# CH32F205RBT6-R1.net
KiCad netlist of a schematic drawn in Altium Designer
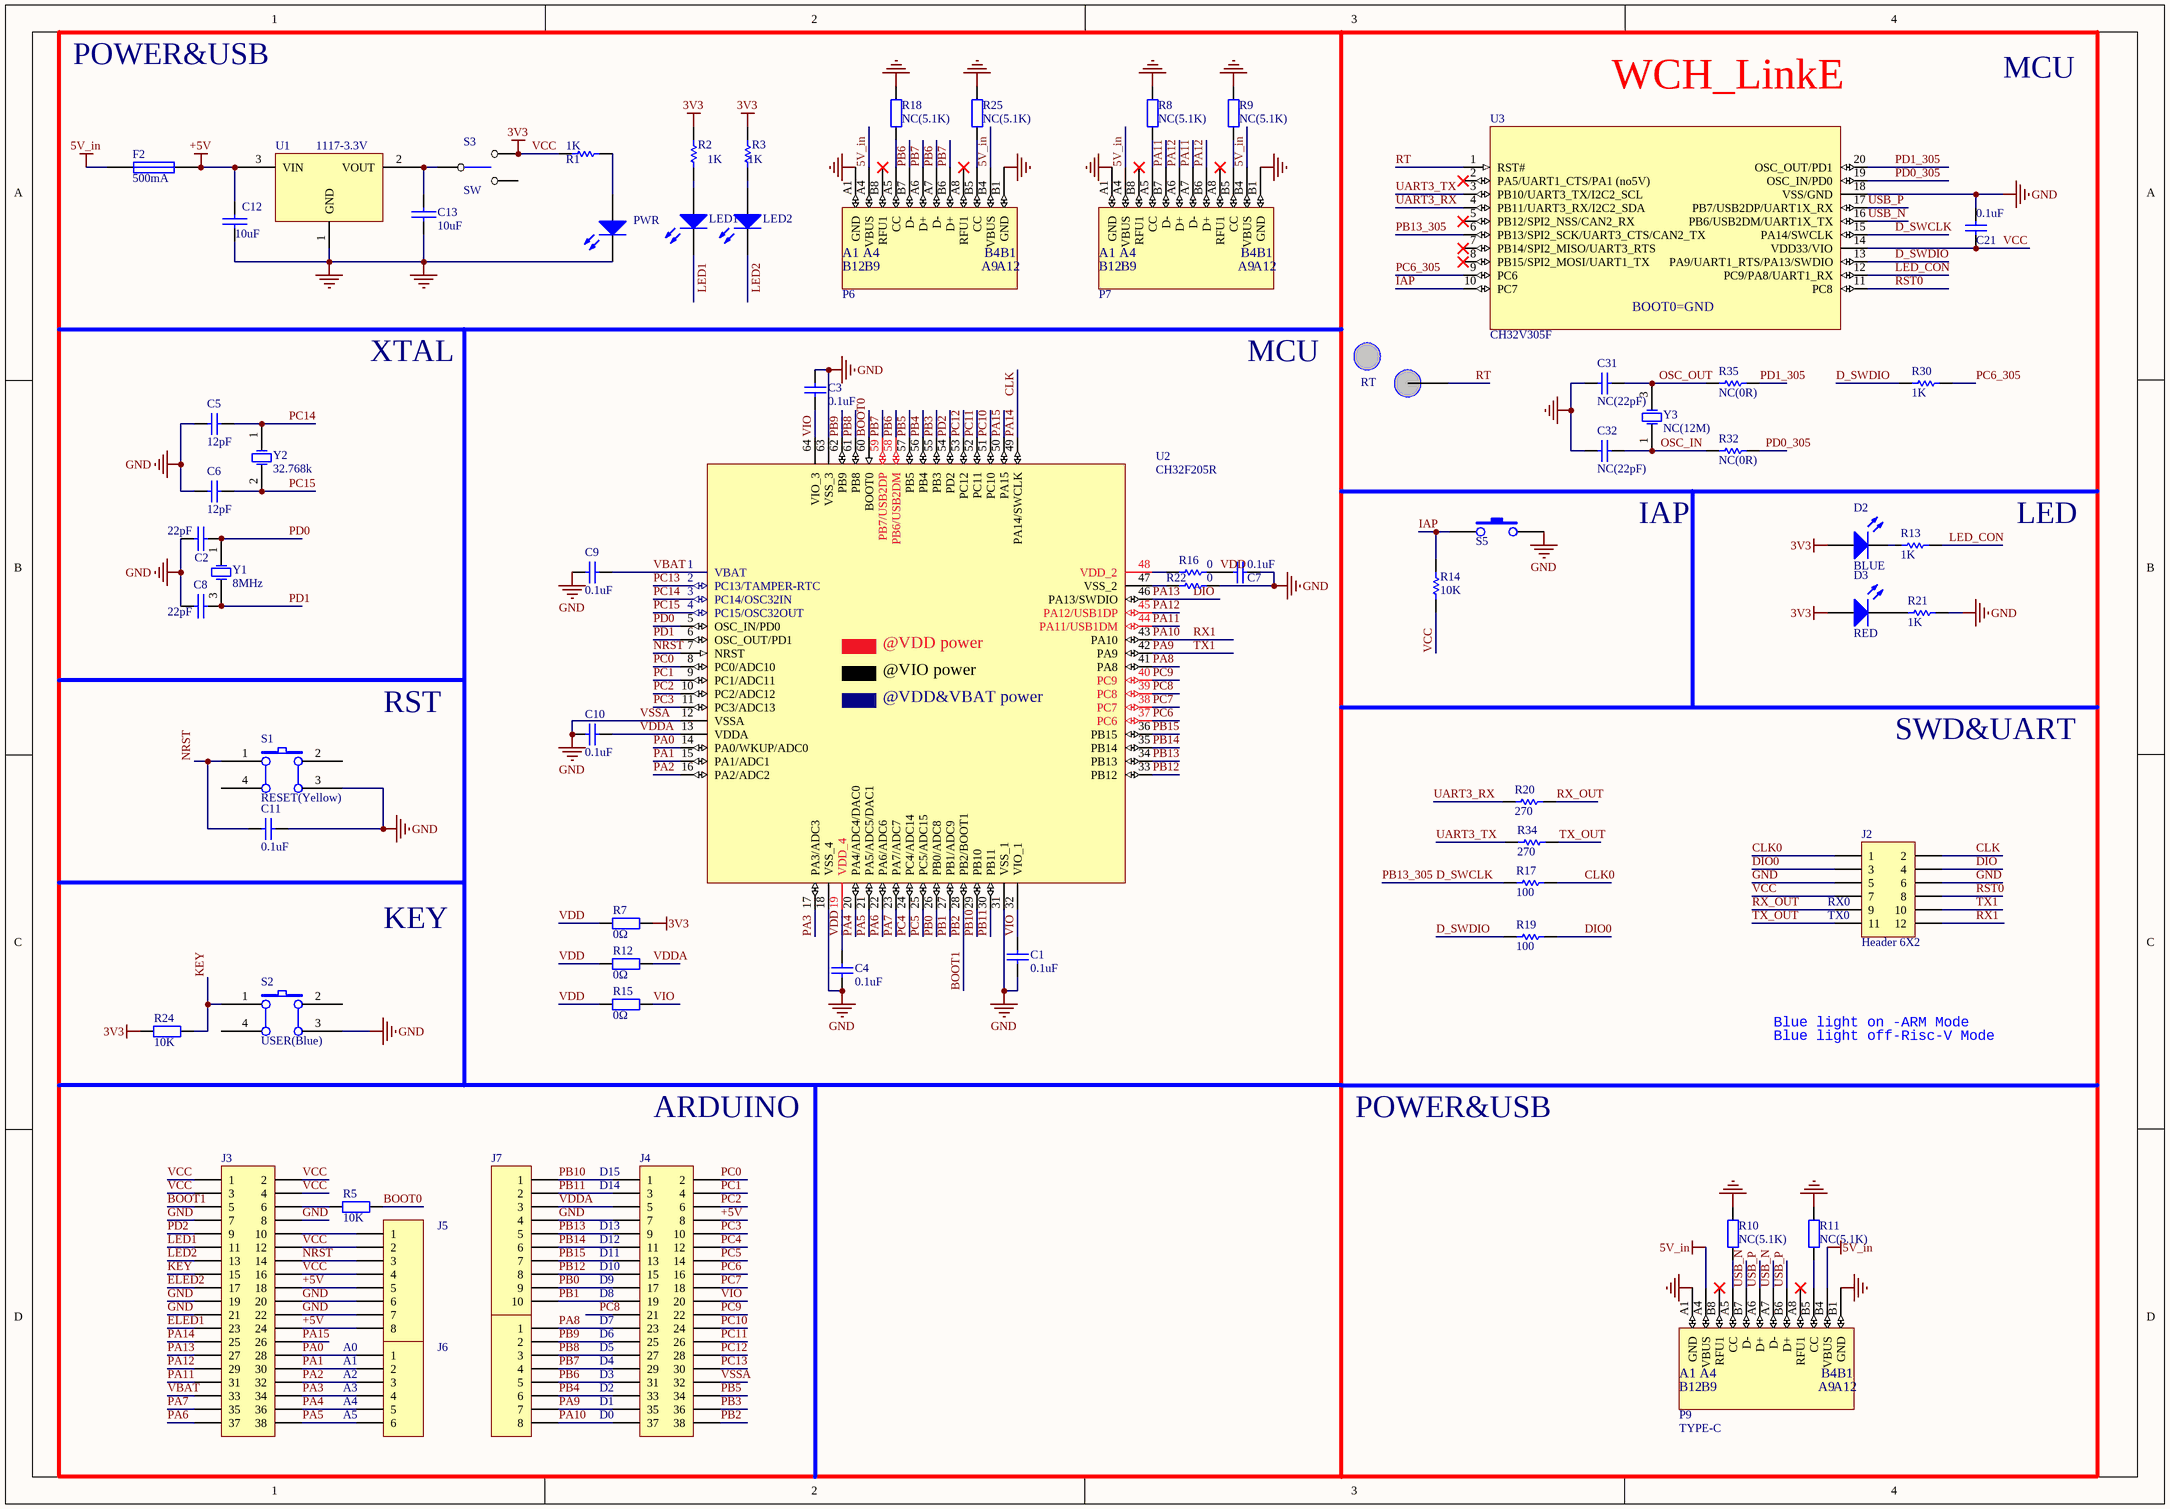
[diagram p0: CH32F205RBT6-R1.SchDoc]

(export (version "E")
  (design (tool "Eeschema 10.0.6"))
  (components
    (comp (ref "C1")
      (value "0.1uF")
      (footprint "0603_C")
      (description "Capacitor")
      (libsource (lib "Miscellaneous Devices") (part "Cap"))
    )
    (comp (ref "C2")
      (value "22pF")
      (footprint "0603_C")
      (description "Capacitor")
      (libsource (lib "*") (part "CAP"))
    )
    (comp (ref "C3")
      (value "0.1uF")
      (footprint "0603_C")
      (description "Capacitor")
      (libsource (lib "Miscellaneous Devices") (part "Cap"))
    )
    (comp (ref "C4")
      (value "0.1uF")
      (footprint "0603_C")
      (description "Capacitor")
      (libsource (lib "Miscellaneous Devices") (part "Cap"))
    )
    (comp (ref "C5")
      (value "12pF")
      (footprint "0603_C")
      (description "Capacitor")
      (libsource (lib "Miscellaneous Devices") (part "Cap"))
    )
    (comp (ref "C6")
      (value "12pF")
      (footprint "0603_C")
      (description "Capacitor")
      (libsource (lib "Miscellaneous Devices") (part "Cap"))
    )
    (comp (ref "C7")
      (value "0.1uF")
      (footprint "0603_C")
      (description "Capacitor")
      (libsource (lib "Miscellaneous Devices") (part "Cap"))
    )
    (comp (ref "C8")
      (value "22pF")
      (footprint "0603_C")
      (description "Capacitor")
      (libsource (lib "*") (part "CAP"))
    )
    (comp (ref "C9")
      (value "0.1uF")
      (footprint "0603_C")
      (description "Capacitor")
      (libsource (lib "Miscellaneous Devices") (part "Cap"))
    )
    (comp (ref "C10")
      (value "0.1uF")
      (footprint "0603_C")
      (description "Capacitor")
      (libsource (lib "Miscellaneous Devices") (part "Cap"))
    )
    (comp (ref "C11")
      (value "0.1uF")
      (footprint "0603_C")
      (description "Capacitor")
      (libsource (lib "Miscellaneous Devices") (part "Cap"))
    )
    (comp (ref "C12")
      (value "10uF")
      (footprint "3216_C")
      (description "Capacitor")
      (libsource (lib "*") (part "CAP"))
    )
    (comp (ref "C13")
      (value "10uF")
      (footprint "3216_C")
      (description "Capacitor")
      (libsource (lib "*") (part "CAP"))
    )
    (comp (ref "C21")
      (value "0.1uF")
      (footprint "0603_C")
      (description "Capacitor")
      (libsource (lib "Miscellaneous Devices") (part "Cap"))
    )
    (comp (ref "C31")
      (value "NC(22pF)")
      (footprint "0603_C")
      (description "Capacitor")
      (fields (field (name "PUBLISHER") "Altium Limited"))
      (libsource (lib "*") (part "Cap"))
    )
    (comp (ref "C32")
      (value "NC(22pF)")
      (footprint "0603_C")
      (description "Capacitor")
      (fields (field (name "PUBLISHER") "Altium Limited"))
      (libsource (lib "*") (part "Cap"))
    )
    (comp (ref "D2")
      (value "BLUE")
      (footprint "0603+")
      (description "Typical RED, GREEN, YELLOW, AMBER GaAs LED")
      (fields (field (name "PUBLISHER") "Altium Limited"))
      (libsource (lib "MYLIB") (part "D0603"))
    )
    (comp (ref "D3")
      (value "RED")
      (footprint "0603+")
      (description "Typical RED, GREEN, YELLOW, AMBER GaAs LED")
      (fields (field (name "PUBLISHER") "Altium Limited"))
      (libsource (lib "MYLIB") (part "D0603"))
    )
    (comp (ref "F2")
      (value "500mA")
      (footprint "0805")
      (description "Fuse")
      (libsource (lib "*") (part "FUSE1"))
    )
    (comp (ref "J2")
      (value "Header 6X2")
      (footprint "IDC12-2.54mm")
      (description "Header, 6-Pin, Dual row")
      (fields (field (name "PUBLISHER") "Altium Limited"))
      (libsource (lib "Miscellaneous Connectors") (part "Header 6X2"))
    )
    (comp (ref "J3")
      (value "Header 19X2")
      (footprint "IDC38-2.54mm")
      (description "Header, 19-Pin, Dual row")
      (fields (field (name "PUBLISHER") "Altium Limited"))
      (libsource (lib "Miscellaneous Connectors") (part "Header 19X2"))
    )
    (comp (ref "J4")
      (value "Header 19X2")
      (footprint "IDC38-2.54mm")
      (description "Header, 19-Pin, Dual row")
      (fields (field (name "PUBLISHER") "Altium Limited"))
      (libsource (lib "Miscellaneous Connectors") (part "Header 19X2"))
    )
    (comp (ref "J5")
      (value "Header 8")
      (footprint "SIP8-2.54mm")
      (description "Header, 8-Pin")
      (fields (field (name "PUBLISHER") "Altium Limited"))
      (libsource (lib "Miscellaneous Connectors") (part "Header 8"))
    )
    (comp (ref "J6")
      (value "Header 6")
      (footprint "SIP6-2.54MM")
      (description "Header, 6-Pin")
      (fields (field (name "PUBLISHER") "Altium Limited"))
      (libsource (lib "Miscellaneous Connectors") (part "Header 6"))
    )
    (comp (ref "J7")
      (value "Header 10")
      (footprint "SIP10-2.54mm")
      (description "Header, 10-Pin")
      (fields (field (name "PUBLISHER") "Altium Limited"))
      (libsource (lib "Miscellaneous Connectors") (part "Header 10"))
    )
    (comp (ref "J8")
      (value "Header 8")
      (footprint "SIP8-2.54mm")
      (description "Header, 8-Pin")
      (fields (field (name "PUBLISHER") "Altium Limited"))
      (libsource (lib "") (part "Header 8_1"))
    )
    (comp (ref "LED1")
      (value "LED1   blue")
      (footprint "0603+")
      (description "Typical INFRARED GaAs LED")
      (fields (field (name "PUBLISHER") "Altium Limited"))
      (libsource (lib "Miscellaneous Devices") (part "LED0"))
    )
    (comp (ref "LED2")
      (value "LED2  blue")
      (footprint "0603+")
      (description "Typical INFRARED GaAs LED")
      (fields (field (name "PUBLISHER") "Altium Limited"))
      (libsource (lib "Miscellaneous Devices") (part "LED0"))
    )
    (comp (ref "P6")
      (value "TYPE-C")
      (footprint "TYPE-C-Receptacle-2.0")
      (libsource (lib "*") (part "TYPE-C1"))
    )
    (comp (ref "P7")
      (value "TYPE-C")
      (footprint "TYPE-C-Receptacle-2.0")
      (libsource (lib "*") (part "TYPE-C1"))
    )
    (comp (ref "P9")
      (value "TYPE-C")
      (footprint "TYPE-C-Receptacle-2.0")
      (libsource (lib "*") (part "TYPE-C1"))
    )
    (comp (ref "PWR")
      (value "POWER  red")
      (footprint "0603+")
      (description "Typical INFRARED GaAs LED")
      (fields (field (name "PUBLISHER") "Altium Limited"))
      (libsource (lib "Miscellaneous Devices") (part "LED0"))
    )
    (comp (ref "R1")
      (value "1K")
      (footprint "0603")
      (description "Semiconductor Resistor")
      (libsource (lib "Miscellaneous Devices") (part "Res Semi"))
    )
    (comp (ref "R2")
      (value "1K")
      (footprint "0603")
      (description "Semiconductor Resistor")
      (libsource (lib "Miscellaneous Devices") (part "Res Semi"))
    )
    (comp (ref "R3")
      (value "1K")
      (footprint "0603")
      (description "Semiconductor Resistor")
      (libsource (lib "Miscellaneous Devices") (part "Res Semi"))
    )
    (comp (ref "R5")
      (value "10K")
      (footprint "0603")
      (description "Resistor")
      (libsource (lib "") (part "Res2_3"))
    )
    (comp (ref "R7")
      (value "0Ω")
      (footprint "0603")
      (description "Resistor")
      (libsource (lib "") (part "Res2_2"))
    )
    (comp (ref "R8")
      (value "NC(5.1K)")
      (footprint "0603")
      (description "Resistor")
      (libsource (lib "Miscellaneous Devices") (part "Res2"))
    )
    (comp (ref "R9")
      (value "NC(5.1K)")
      (footprint "0603")
      (description "Resistor")
      (libsource (lib "Miscellaneous Devices") (part "Res2"))
    )
    (comp (ref "R10")
      (value "NC(5.1K)")
      (footprint "0603")
      (description "Resistor")
      (libsource (lib "") (part "Res2_1"))
    )
    (comp (ref "R11")
      (value "NC(5.1K)")
      (footprint "0603")
      (description "Resistor")
      (libsource (lib "") (part "Res2_1"))
    )
    (comp (ref "R12")
      (value "0Ω")
      (footprint "0603")
      (description "Resistor")
      (libsource (lib "") (part "Res2_2"))
    )
    (comp (ref "R13")
      (value "1K")
      (footprint "0603")
      (description "Resistor")
      (fields (field (name "PUBLISHER") "Altium Limited"))
      (libsource (lib "MYLIB") (part "0603-1"))
    )
    (comp (ref "R14")
      (value "10K")
      (footprint "0603")
      (description "Resistor")
      (fields (field (name "PUBLISHER") "Altium Limited"))
      (libsource (lib "MYLIB") (part "0603-1"))
    )
    (comp (ref "R15")
      (value "0Ω")
      (footprint "0603")
      (description "Resistor")
      (libsource (lib "") (part "Res2_2"))
    )
    (comp (ref "R16")
      (value "0")
      (footprint "0603")
      (description "Resistor")
      (fields (field (name "PUBLISHER") "Altium Limited"))
      (libsource (lib "MYLIB") (part "0603-1"))
    )
    (comp (ref "R17")
      (value "100")
      (footprint "0603")
      (description "Resistor")
      (fields (field (name "PUBLISHER") "Altium Limited"))
      (libsource (lib "MYLIB") (part "0603-1"))
    )
    (comp (ref "R18")
      (value "NC(5.1K)")
      (footprint "0603")
      (description "Resistor")
      (libsource (lib "Miscellaneous Devices") (part "Res2"))
    )
    (comp (ref "R19")
      (value "100")
      (footprint "0603")
      (description "Resistor")
      (fields (field (name "PUBLISHER") "Altium Limited"))
      (libsource (lib "MYLIB") (part "0603-1"))
    )
    (comp (ref "R20")
      (value "270")
      (footprint "0603")
      (description "Resistor")
      (fields (field (name "PUBLISHER") "Altium Limited"))
      (libsource (lib "MYLIB") (part "0603-1"))
    )
    (comp (ref "R21")
      (value "1K")
      (footprint "0603")
      (description "Resistor")
      (fields (field (name "PUBLISHER") "Altium Limited"))
      (libsource (lib "MYLIB") (part "0603-1"))
    )
    (comp (ref "R22")
      (value "0")
      (footprint "0603")
      (description "Resistor")
      (fields (field (name "PUBLISHER") "Altium Limited"))
      (libsource (lib "MYLIB") (part "0603-1"))
    )
    (comp (ref "R24")
      (value "10K")
      (footprint "0603")
      (description "Resistor")
      (libsource (lib "") (part "Res2_2"))
    )
    (comp (ref "R25")
      (value "NC(5.1K)")
      (footprint "0603")
      (description "Resistor")
      (libsource (lib "Miscellaneous Devices") (part "Res2"))
    )
    (comp (ref "R30")
      (value "1K")
      (footprint "0603")
      (description "Resistor")
      (fields (field (name "PUBLISHER") "Altium Limited"))
      (libsource (lib "MYLIB") (part "0603-1"))
    )
    (comp (ref "R32")
      (value "NC(0R)")
      (footprint "0603")
      (description "Resistor")
      (fields (field (name "PUBLISHER") "Altium Limited"))
      (libsource (lib "MYLIB") (part "0603-1"))
    )
    (comp (ref "R34")
      (value "270")
      (footprint "0603")
      (description "Resistor")
      (fields (field (name "PUBLISHER") "Altium Limited"))
      (libsource (lib "MYLIB") (part "0603-1"))
    )
    (comp (ref "R35")
      (value "NC(0R)")
      (footprint "0603")
      (description "Resistor")
      (fields (field (name "PUBLISHER") "Altium Limited"))
      (libsource (lib "MYLIB") (part "0603-1"))
    )
    (comp (ref "RT")
      (value "Testpoint")
      (footprint "TESTPOINT1")
      (description "测试点")
      (libsource (lib "wch_sch_others") (part "Testpoint"))
    )
    (comp (ref "S1")
      (value "RESET(Yellow)")
      (footprint "KEYX")
      (description "SE PUSHBUTTON")
      (libsource (lib "Documents") (part "SW PUSHBUTTON"))
    )
    (comp (ref "S2")
      (value "USER(Blue)")
      (footprint "KEYX")
      (description "SE PUSHBUTTON")
      (libsource (lib "Documents") (part "SW PUSHBUTTON"))
    )
    (comp (ref "S3") (value "SW") (footprint "SW1") (libsource (lib "MYSCH") (part "SW")))
    (comp (ref "S5") (value "KEY") (footprint "贴片按键") (libsource (lib "*") (part "KEY")))
    (comp (ref "U1")
      (value "1117-3.3V")
      (footprint "SOT-223")
      (libsource (lib "wch_sch_others") (part "1117-3.3V"))
    )
    (comp (ref "U2")
      (value "CH32F205R")
      (footprint "LQFP64M_10x10")
      (description "ARM M3 HD-MCU, 144MHz, USB_480M, USB OTG, 2*CAN, 4*OPA")
      (libsource (lib "CHXXX") (part "CH32F205R"))
    )
    (comp (ref "U3")
      (value "CH32V305F")
      (footprint "TSSOP20")
      (description "RISC-V FPU HD-MCU, 144MHz, USB_480M, CAN, UART*2, SPI")
      (libsource (lib "CHXXX") (part "CH32V305F"))
    )
    (comp (ref "Y1")
      (value "8MHz")
      (footprint "XT3225")
      (description "Crystal Oscillator")
      (fields (field (name "PUBLISHER") "Altium Limited"))
      (libsource (lib "*") (part "XTAL"))
    )
    (comp (ref "Y2")
      (value "32.768k")
      (footprint "FC-135")
      (description "Crystal Oscillator")
      (fields (field (name "PUBLISHER") "Altium Limited"))
      (libsource (lib "Miscellaneous Devices") (part "XTAL"))
    )
    (comp (ref "Y3")
      (value "NC(12M)")
      (footprint "XT3225")
      (description "Crystal Oscillator")
      (libsource (lib "*") (part "XTAL"))
    )
  )
  (nets
    (net (code "1") (name "+5V") (class "Default")
      (node (ref "C12") (pin "1") (pinfunction "1_1") (pintype "passive"))
      (node (ref "F2") (pin "2") (pinfunction "2_2") (pintype "passive"))
      (node (ref "J3") (pin "18") (pinfunction "18_18") (pintype "passive"))
      (node (ref "J3") (pin "24") (pinfunction "24_24") (pintype "passive"))
      (node (ref "J4") (pin "8") (pinfunction "8_8") (pintype "passive"))
      (node (ref "J5") (pin "5") (pinfunction "5_5") (pintype "passive"))
      (node (ref "J5") (pin "8") (pinfunction "8_8") (pintype "passive"))
      (node (ref "U1") (pin "3") (pinfunction "VIN_3") (pintype "passive"))
    )
    (net (code "2") (name "/BOOT0") (class "Default")
      (node (ref "R5") (pin "2") (pinfunction "2_2") (pintype "passive"))
      (node (ref "U2") (pin "60") (pinfunction "BOOT0_60") (pintype "input"))
    )
    (net (code "3") (name "/BOOT1") (class "Default")
      (node (ref "J3") (pin "5") (pinfunction "5_5") (pintype "passive"))
      (node (ref "J4") (pin "38") (pinfunction "38_38") (pintype "passive"))
      (node (ref "U2") (pin "28") (pinfunction "PB2/BOOT1_28") (pintype "bidirectional"))
    )
    (net (code "4") (name "/CLK") (class "Default")
      (node (ref "J2") (pin "2") (pinfunction "2_2") (pintype "passive"))
      (node (ref "J3") (pin "25") (pinfunction "25_25") (pintype "passive"))
      (node (ref "U2") (pin "49") (pinfunction "PA14/SWCLK_49") (pintype "bidirectional"))
    )
    (net (code "5") (name "/CLK0") (class "Default")
      (node (ref "J2") (pin "1") (pinfunction "1_1") (pintype "passive"))
      (node (ref "R17") (pin "1") (pinfunction "1_1") (pintype "passive"))
    )
    (net (code "6") (name "/DIO") (class "Default")
      (node (ref "J2") (pin "4") (pinfunction "4_4") (pintype "passive"))
      (node (ref "J3") (pin "27") (pinfunction "27_27") (pintype "passive"))
      (node (ref "U2") (pin "46") (pinfunction "PA13/SWDIO_46") (pintype "bidirectional"))
    )
    (net (code "7") (name "/DIO0") (class "Default")
      (node (ref "J2") (pin "3") (pinfunction "3_3") (pintype "passive"))
      (node (ref "R19") (pin "1") (pinfunction "1_1") (pintype "passive"))
    )
    (net (code "8") (name "/D_SWCLK") (class "Default")
      (node (ref "R17") (pin "2") (pinfunction "2_2") (pintype "passive"))
      (node (ref "U3") (pin "15") (pinfunction "PA14/SWCLK_15") (pintype "bidirectional"))
      (node (ref "U3") (pin "6") (pinfunction "PB13/SPI2_SCK/UART3_CTS/CAN2_TX_6") (pintype "bidirectional"))
    )
    (net (code "9") (name "/D_SWDIO") (class "Default")
      (node (ref "R19") (pin "2") (pinfunction "2_2") (pintype "passive"))
      (node (ref "R30") (pin "1") (pinfunction "1_1") (pintype "passive"))
      (node (ref "U3") (pin "13") (pinfunction "PA9/UART1_RTS/PA13/SWDIO_13") (pintype "bidirectional"))
    )
    (net (code "10") (name "/ELED1") (class "Default")
      (node (ref "J3") (pin "23") (pinfunction "23_23") (pintype "passive"))
    )
    (net (code "11") (name "/ELED2") (class "Default")
      (node (ref "J3") (pin "17") (pinfunction "17_17") (pintype "passive"))
    )
    (net (code "12") (name "/IAP") (class "Default")
      (node (ref "R14") (pin "1") (pinfunction "1_1") (pintype "passive"))
      (node (ref "S5") (pin "1") (pinfunction "1_1") (pintype "passive"))
      (node (ref "U3") (pin "10") (pinfunction "PC7_10") (pintype "bidirectional"))
    )
    (net (code "13") (name "/KEY") (class "Default")
      (node (ref "J3") (pin "15") (pinfunction "15_15") (pintype "passive"))
      (node (ref "R24") (pin "1") (pinfunction "1_1") (pintype "passive"))
      (node (ref "S2") (pin "1") (pinfunction "A0_1") (pintype "passive"))
    )
    (net (code "14") (name "/LED1") (class "Default")
      (node (ref "J3") (pin "11") (pinfunction "11_11") (pintype "passive"))
      (node (ref "LED1") (pin "2") (pinfunction "K_2") (pintype "passive"))
    )
    (net (code "15") (name "/LED2") (class "Default")
      (node (ref "J3") (pin "13") (pinfunction "13_13") (pintype "passive"))
      (node (ref "LED2") (pin "2") (pinfunction "K_2") (pintype "passive"))
    )
    (net (code "16") (name "/LED_CON") (class "Default")
      (node (ref "R13") (pin "1") (pinfunction "1_1") (pintype "passive"))
      (node (ref "U3") (pin "12") (pinfunction "PC9/PA8/UART1_RX_12") (pintype "bidirectional"))
    )
    (net (code "17") (name "/NRST") (class "Default")
      (node (ref "C11") (pin "2") (pinfunction "2_2") (pintype "passive"))
      (node (ref "J3") (pin "14") (pinfunction "14_14") (pintype "passive"))
      (node (ref "J5") (pin "3") (pinfunction "3_3") (pintype "passive"))
      (node (ref "S1") (pin "1") (pinfunction "A0_1") (pintype "passive"))
      (node (ref "U2") (pin "7") (pinfunction "NRST_7") (pintype "input"))
    )
    (net (code "18") (name "/OSC_IN") (class "Default")
      (node (ref "C32") (pin "2") (pinfunction "2_2") (pintype "passive"))
      (node (ref "R32") (pin "2") (pinfunction "2_2") (pintype "passive"))
      (node (ref "Y3") (pin "1") (pinfunction "OSC1_1") (pintype "passive"))
    )
    (net (code "19") (name "/OSC_OUT") (class "Default")
      (node (ref "C31") (pin "2") (pinfunction "2_2") (pintype "passive"))
      (node (ref "R35") (pin "2") (pinfunction "2_2") (pintype "passive"))
      (node (ref "Y3") (pin "3") (pinfunction "OSC2_3") (pintype "passive"))
    )
    (net (code "20") (name "/PA0") (class "Default")
      (node (ref "J3") (pin "28") (pinfunction "28_28") (pintype "passive"))
      (node (ref "J6") (pin "1") (pinfunction "1_1") (pintype "passive"))
      (node (ref "U2") (pin "14") (pinfunction "PA0/WKUP/ADC0_14") (pintype "bidirectional"))
    )
    (net (code "21") (name "/PA1") (class "Default")
      (node (ref "J3") (pin "30") (pinfunction "30_30") (pintype "passive"))
      (node (ref "J6") (pin "2") (pinfunction "2_2") (pintype "passive"))
      (node (ref "U2") (pin "15") (pinfunction "PA1/ADC1_15") (pintype "bidirectional"))
    )
    (net (code "22") (name "/PA2") (class "Default")
      (node (ref "J3") (pin "32") (pinfunction "32_32") (pintype "passive"))
      (node (ref "J6") (pin "3") (pinfunction "3_3") (pintype "passive"))
      (node (ref "U2") (pin "16") (pinfunction "PA2/ADC2_16") (pintype "bidirectional"))
    )
    (net (code "23") (name "/PA3") (class "Default")
      (node (ref "J3") (pin "34") (pinfunction "34_34") (pintype "passive"))
      (node (ref "J6") (pin "4") (pinfunction "4_4") (pintype "passive"))
      (node (ref "U2") (pin "17") (pinfunction "PA3/ADC3_17") (pintype "bidirectional"))
    )
    (net (code "24") (name "/PA4") (class "Default")
      (node (ref "J3") (pin "36") (pinfunction "36_36") (pintype "passive"))
      (node (ref "J6") (pin "5") (pinfunction "5_5") (pintype "passive"))
      (node (ref "U2") (pin "20") (pinfunction "PA4/ADC4/DAC0_20") (pintype "bidirectional"))
    )
    (net (code "25") (name "/PA5") (class "Default")
      (node (ref "J3") (pin "38") (pinfunction "38_38") (pintype "passive"))
      (node (ref "J6") (pin "6") (pinfunction "6_6") (pintype "passive"))
      (node (ref "U2") (pin "21") (pinfunction "PA5/ADC5/DAC1_21") (pintype "bidirectional"))
    )
    (net (code "26") (name "/PA6") (class "Default")
      (node (ref "J3") (pin "37") (pinfunction "37_37") (pintype "passive"))
      (node (ref "U2") (pin "22") (pinfunction "PA6/ADC6_22") (pintype "bidirectional"))
    )
    (net (code "27") (name "/PA7") (class "Default")
      (node (ref "J3") (pin "35") (pinfunction "35_35") (pintype "passive"))
      (node (ref "U2") (pin "23") (pinfunction "PA7/ADC7_23") (pintype "bidirectional"))
    )
    (net (code "28") (name "/PA8") (class "Default")
      (node (ref "J4") (pin "23") (pinfunction "23_23") (pintype "passive"))
      (node (ref "J8") (pin "1") (pinfunction "1_1") (pintype "passive"))
      (node (ref "U2") (pin "41") (pinfunction "PA8_41") (pintype "bidirectional"))
    )
    (net (code "29") (name "/PA9") (class "Default")
      (node (ref "J2") (pin "10") (pinfunction "10_10") (pintype "passive"))
      (node (ref "J4") (pin "35") (pinfunction "35_35") (pintype "passive"))
      (node (ref "J8") (pin "7") (pinfunction "7_7") (pintype "passive"))
      (node (ref "U2") (pin "42") (pinfunction "PA9_42") (pintype "bidirectional"))
    )
    (net (code "30") (name "/PA10") (class "Default")
      (node (ref "J2") (pin "12") (pinfunction "12_12") (pintype "passive"))
      (node (ref "J4") (pin "37") (pinfunction "37_37") (pintype "passive"))
      (node (ref "J8") (pin "8") (pinfunction "8_8") (pintype "passive"))
      (node (ref "U2") (pin "43") (pinfunction "PA10_43") (pintype "bidirectional"))
    )
    (net (code "31") (name "/PA11") (class "Default")
      (node (ref "J3") (pin "31") (pinfunction "31_31") (pintype "passive"))
      (node (ref "P7") (pin "A7") (pinfunction "D-_A7") (pintype "bidirectional"))
      (node (ref "P7") (pin "B7") (pinfunction "D-_B7") (pintype "bidirectional"))
      (node (ref "U2") (pin "44") (pinfunction "PA11/USB1DM_44") (pintype "bidirectional"))
    )
    (net (code "32") (name "/PA12") (class "Default")
      (node (ref "J3") (pin "29") (pinfunction "29_29") (pintype "passive"))
      (node (ref "P7") (pin "A6") (pinfunction "D+_A6") (pintype "bidirectional"))
      (node (ref "P7") (pin "B6") (pinfunction "D+_B6") (pintype "bidirectional"))
      (node (ref "U2") (pin "45") (pinfunction "PA12/USB1DP_45") (pintype "bidirectional"))
    )
    (net (code "33") (name "/PA15") (class "Default")
      (node (ref "J3") (pin "26") (pinfunction "26_26") (pintype "passive"))
      (node (ref "U2") (pin "50") (pinfunction "PA15_50") (pintype "bidirectional"))
    )
    (net (code "34") (name "/PB0") (class "Default")
      (node (ref "J4") (pin "17") (pinfunction "17_17") (pintype "passive"))
      (node (ref "J7") (pin "9") (pinfunction "9_9") (pintype "passive"))
      (node (ref "U2") (pin "26") (pinfunction "PB0/ADC8_26") (pintype "bidirectional"))
    )
    (net (code "35") (name "/PB1") (class "Default")
      (node (ref "J4") (pin "19") (pinfunction "19_19") (pintype "passive"))
      (node (ref "J7") (pin "10") (pinfunction "10_10") (pintype "passive"))
      (node (ref "U2") (pin "27") (pinfunction "PB1/ADC9_27") (pintype "bidirectional"))
    )
    (net (code "36") (name "/PB3") (class "Default")
      (node (ref "J4") (pin "36") (pinfunction "36_36") (pintype "passive"))
      (node (ref "U2") (pin "55") (pinfunction "PB3_55") (pintype "bidirectional"))
    )
    (net (code "37") (name "/PB4") (class "Default")
      (node (ref "J4") (pin "33") (pinfunction "33_33") (pintype "passive"))
      (node (ref "J8") (pin "6") (pinfunction "6_6") (pintype "passive"))
      (node (ref "U2") (pin "56") (pinfunction "PB4_56") (pintype "bidirectional"))
    )
    (net (code "38") (name "/PB5") (class "Default")
      (node (ref "J4") (pin "34") (pinfunction "34_34") (pintype "passive"))
      (node (ref "U2") (pin "57") (pinfunction "PB5_57") (pintype "bidirectional"))
    )
    (net (code "39") (name "/PB6") (class "Default")
      (node (ref "J4") (pin "31") (pinfunction "31_31") (pintype "passive"))
      (node (ref "J8") (pin "5") (pinfunction "5_5") (pintype "passive"))
      (node (ref "P6") (pin "A7") (pinfunction "D-_A7") (pintype "bidirectional"))
      (node (ref "P6") (pin "B7") (pinfunction "D-_B7") (pintype "bidirectional"))
      (node (ref "U2") (pin "58") (pinfunction "PB6/USB2DM_58") (pintype "bidirectional"))
    )
    (net (code "40") (name "/PB7") (class "Default")
      (node (ref "J4") (pin "29") (pinfunction "29_29") (pintype "passive"))
      (node (ref "J8") (pin "4") (pinfunction "4_4") (pintype "passive"))
      (node (ref "P6") (pin "A6") (pinfunction "D+_A6") (pintype "bidirectional"))
      (node (ref "P6") (pin "B6") (pinfunction "D+_B6") (pintype "bidirectional"))
      (node (ref "U2") (pin "59") (pinfunction "PB7/USB2DP_59") (pintype "bidirectional"))
    )
    (net (code "41") (name "/PB8") (class "Default")
      (node (ref "J4") (pin "27") (pinfunction "27_27") (pintype "passive"))
      (node (ref "J8") (pin "3") (pinfunction "3_3") (pintype "passive"))
      (node (ref "U2") (pin "61") (pinfunction "PB8_61") (pintype "bidirectional"))
    )
    (net (code "42") (name "/PB9") (class "Default")
      (node (ref "J4") (pin "25") (pinfunction "25_25") (pintype "passive"))
      (node (ref "J8") (pin "2") (pinfunction "2_2") (pintype "passive"))
      (node (ref "U2") (pin "62") (pinfunction "PB9_62") (pintype "bidirectional"))
    )
    (net (code "43") (name "/PB10") (class "Default")
      (node (ref "J4") (pin "1") (pinfunction "1_1") (pintype "passive"))
      (node (ref "J7") (pin "1") (pinfunction "1_1") (pintype "passive"))
      (node (ref "U2") (pin "29") (pinfunction "PB10_29") (pintype "bidirectional"))
    )
    (net (code "44") (name "/PB11") (class "Default")
      (node (ref "J4") (pin "3") (pinfunction "3_3") (pintype "passive"))
      (node (ref "J7") (pin "2") (pinfunction "2_2") (pintype "passive"))
      (node (ref "U2") (pin "30") (pinfunction "PB11_30") (pintype "bidirectional"))
    )
    (net (code "45") (name "/PB12") (class "Default")
      (node (ref "J4") (pin "15") (pinfunction "15_15") (pintype "passive"))
      (node (ref "J7") (pin "8") (pinfunction "8_8") (pintype "passive"))
      (node (ref "U2") (pin "33") (pinfunction "PB12_33") (pintype "bidirectional"))
    )
    (net (code "46") (name "/PB13") (class "Default")
      (node (ref "J4") (pin "9") (pinfunction "9_9") (pintype "passive"))
      (node (ref "J7") (pin "5") (pinfunction "5_5") (pintype "passive"))
      (node (ref "U2") (pin "34") (pinfunction "PB13_34") (pintype "bidirectional"))
    )
    (net (code "47") (name "/PB14") (class "Default")
      (node (ref "J4") (pin "11") (pinfunction "11_11") (pintype "passive"))
      (node (ref "J7") (pin "6") (pinfunction "6_6") (pintype "passive"))
      (node (ref "U2") (pin "35") (pinfunction "PB14_35") (pintype "bidirectional"))
    )
    (net (code "48") (name "/PB15") (class "Default")
      (node (ref "J4") (pin "13") (pinfunction "13_13") (pintype "passive"))
      (node (ref "J7") (pin "7") (pinfunction "7_7") (pintype "passive"))
      (node (ref "U2") (pin "36") (pinfunction "PB15_36") (pintype "bidirectional"))
    )
    (net (code "49") (name "/PC0") (class "Default")
      (node (ref "J4") (pin "2") (pinfunction "2_2") (pintype "passive"))
      (node (ref "U2") (pin "8") (pinfunction "PC0/ADC10_8") (pintype "bidirectional"))
    )
    (net (code "50") (name "/PC1") (class "Default")
      (node (ref "J4") (pin "4") (pinfunction "4_4") (pintype "passive"))
      (node (ref "U2") (pin "9") (pinfunction "PC1/ADC11_9") (pintype "bidirectional"))
    )
    (net (code "51") (name "/PC2") (class "Default")
      (node (ref "J4") (pin "6") (pinfunction "6_6") (pintype "passive"))
      (node (ref "U2") (pin "10") (pinfunction "PC2/ADC12_10") (pintype "bidirectional"))
    )
    (net (code "52") (name "/PC3") (class "Default")
      (node (ref "J4") (pin "10") (pinfunction "10_10") (pintype "passive"))
      (node (ref "U2") (pin "11") (pinfunction "PC3/ADC13_11") (pintype "bidirectional"))
    )
    (net (code "53") (name "/PC4") (class "Default")
      (node (ref "J4") (pin "12") (pinfunction "12_12") (pintype "passive"))
      (node (ref "U2") (pin "24") (pinfunction "PC4/ADC14_24") (pintype "bidirectional"))
    )
    (net (code "54") (name "/PC5") (class "Default")
      (node (ref "J4") (pin "14") (pinfunction "14_14") (pintype "passive"))
      (node (ref "U2") (pin "25") (pinfunction "PC5/ADC15_25") (pintype "bidirectional"))
    )
    (net (code "55") (name "/PC6") (class "Default")
      (node (ref "J4") (pin "16") (pinfunction "16_16") (pintype "passive"))
      (node (ref "U2") (pin "37") (pinfunction "PC6_37") (pintype "bidirectional"))
    )
    (net (code "56") (name "/PC6_305") (class "Default")
      (node (ref "R30") (pin "2") (pinfunction "2_2") (pintype "passive"))
      (node (ref "U3") (pin "9") (pinfunction "PC6_9") (pintype "bidirectional"))
    )
    (net (code "57") (name "/PC7") (class "Default")
      (node (ref "J4") (pin "18") (pinfunction "18_18") (pintype "passive"))
      (node (ref "U2") (pin "38") (pinfunction "PC7_38") (pintype "bidirectional"))
    )
    (net (code "58") (name "/PC8") (class "Default")
      (node (ref "J4") (pin "21") (pinfunction "21_21") (pintype "passive"))
      (node (ref "U2") (pin "39") (pinfunction "PC8_39") (pintype "bidirectional"))
    )
    (net (code "59") (name "/PC9") (class "Default")
      (node (ref "J4") (pin "22") (pinfunction "22_22") (pintype "passive"))
      (node (ref "U2") (pin "40") (pinfunction "PC9_40") (pintype "bidirectional"))
    )
    (net (code "60") (name "/PC10") (class "Default")
      (node (ref "J4") (pin "24") (pinfunction "24_24") (pintype "passive"))
      (node (ref "U2") (pin "51") (pinfunction "PC10_51") (pintype "bidirectional"))
    )
    (net (code "61") (name "/PC11") (class "Default")
      (node (ref "J4") (pin "26") (pinfunction "26_26") (pintype "passive"))
      (node (ref "U2") (pin "52") (pinfunction "PC11_52") (pintype "bidirectional"))
    )
    (net (code "62") (name "/PC12") (class "Default")
      (node (ref "J4") (pin "28") (pinfunction "28_28") (pintype "passive"))
      (node (ref "U2") (pin "53") (pinfunction "PC12_53") (pintype "bidirectional"))
    )
    (net (code "63") (name "/PC13") (class "Default")
      (node (ref "J4") (pin "30") (pinfunction "30_30") (pintype "passive"))
      (node (ref "U2") (pin "2") (pinfunction "PC13/TAMPER-RTC_2") (pintype "bidirectional"))
    )
    (net (code "64") (name "/PC14") (class "Default")
      (node (ref "C5") (pin "1") (pinfunction "1_1") (pintype "passive"))
      (node (ref "U2") (pin "3") (pinfunction "PC14/OSC32IN_3") (pintype "bidirectional"))
      (node (ref "Y2") (pin "1") (pinfunction "OSC1_1") (pintype "passive"))
    )
    (net (code "65") (name "/PC15") (class "Default")
      (node (ref "C6") (pin "1") (pinfunction "1_1") (pintype "passive"))
      (node (ref "U2") (pin "4") (pinfunction "PC15/OSC32OUT_4") (pintype "bidirectional"))
      (node (ref "Y2") (pin "2") (pinfunction "OSC2_2") (pintype "passive"))
    )
    (net (code "66") (name "/PD0") (class "Default")
      (node (ref "C2") (pin "2") (pinfunction "2_2") (pintype "passive"))
      (node (ref "U2") (pin "5") (pinfunction "OSC_IN/PD0_5") (pintype "bidirectional"))
      (node (ref "Y1") (pin "1") (pinfunction "OSC1_1") (pintype "passive"))
    )
    (net (code "67") (name "/PD0_305") (class "Default")
      (node (ref "R32") (pin "1") (pinfunction "1_1") (pintype "passive"))
      (node (ref "U3") (pin "19") (pinfunction "OSC_IN/PD0_19") (pintype "bidirectional"))
    )
    (net (code "68") (name "/PD1") (class "Default")
      (node (ref "C8") (pin "2") (pinfunction "2_2") (pintype "passive"))
      (node (ref "U2") (pin "6") (pinfunction "OSC_OUT/PD1_6") (pintype "bidirectional"))
      (node (ref "Y1") (pin "3") (pinfunction "OSC2_3") (pintype "passive"))
    )
    (net (code "69") (name "/PD1_305") (class "Default")
      (node (ref "R35") (pin "1") (pinfunction "1_1") (pintype "passive"))
      (node (ref "U3") (pin "20") (pinfunction "OSC_OUT/PD1_20") (pintype "bidirectional"))
    )
    (net (code "70") (name "/PD2") (class "Default")
      (node (ref "J3") (pin "9") (pinfunction "9_9") (pintype "passive"))
      (node (ref "U2") (pin "54") (pinfunction "PD2_54") (pintype "bidirectional"))
    )
    (net (code "71") (name "/RST0") (class "Default")
      (node (ref "J2") (pin "8") (pinfunction "8_8") (pintype "passive"))
      (node (ref "U3") (pin "11") (pinfunction "PC8_11") (pintype "bidirectional"))
    )
    (net (code "72") (name "/RT") (class "Default")
      (node (ref "RT") (pin "1") (pinfunction "point_1") (pintype "passive"))
      (node (ref "U3") (pin "1") (pinfunction "RST#_1") (pintype "input"))
    )
    (net (code "73") (name "/RX_OUT") (class "Default")
      (node (ref "J2") (pin "9") (pinfunction "9_9") (pintype "passive"))
      (node (ref "R20") (pin "1") (pinfunction "1_1") (pintype "passive"))
    )
    (net (code "74") (name "/TX_OUT") (class "Default")
      (node (ref "J2") (pin "11") (pinfunction "11_11") (pintype "passive"))
      (node (ref "R34") (pin "1") (pinfunction "1_1") (pintype "passive"))
    )
    (net (code "75") (name "/UART3_RX") (class "Default")
      (node (ref "R20") (pin "2") (pinfunction "2_2") (pintype "passive"))
      (node (ref "U3") (pin "4") (pinfunction "PB11/UART3_RX/I2C2_SDA_4") (pintype "bidirectional"))
    )
    (net (code "76") (name "/UART3_TX") (class "Default")
      (node (ref "R34") (pin "2") (pinfunction "2_2") (pintype "passive"))
      (node (ref "U3") (pin "3") (pinfunction "PB10/UART3_TX/I2C2_SCL_3") (pintype "bidirectional"))
    )
    (net (code "77") (name "/USB_N") (class "Default")
      (node (ref "P9") (pin "A7") (pinfunction "D-_A7") (pintype "bidirectional"))
      (node (ref "P9") (pin "B7") (pinfunction "D-_B7") (pintype "bidirectional"))
      (node (ref "U3") (pin "16") (pinfunction "PB6/USB2DM/UART1X_TX_16") (pintype "bidirectional"))
    )
    (net (code "78") (name "/USB_P") (class "Default")
      (node (ref "P9") (pin "A6") (pinfunction "D+_A6") (pintype "bidirectional"))
      (node (ref "P9") (pin "B6") (pinfunction "D+_B6") (pintype "bidirectional"))
      (node (ref "U3") (pin "17") (pinfunction "PB7/USB2DP/UART1X_RX_17") (pintype "bidirectional"))
    )
    (net (code "79") (name "/VBAT") (class "Default")
      (node (ref "C9") (pin "1") (pinfunction "1_1") (pintype "passive"))
      (node (ref "J3") (pin "33") (pinfunction "33_33") (pintype "passive"))
      (node (ref "U2") (pin "1") (pinfunction "VBAT_1") (pintype "power_in"))
    )
    (net (code "80") (name "/VDD") (class "Default")
      (node (ref "C4") (pin "2") (pinfunction "2_2") (pintype "passive"))
      (node (ref "C7") (pin "2") (pinfunction "2_2") (pintype "passive"))
      (node (ref "R12") (pin "2") (pinfunction "2_2") (pintype "passive"))
      (node (ref "R15") (pin "2") (pinfunction "2_2") (pintype "passive"))
      (node (ref "R16") (pin "1") (pinfunction "1_1") (pintype "passive"))
      (node (ref "R7") (pin "2") (pinfunction "2_2") (pintype "passive"))
      (node (ref "U2") (pin "19") (pinfunction "VDD_4_19") (pintype "power_in"))
    )
    (net (code "81") (name "/VDDA") (class "Default")
      (node (ref "C10") (pin "1") (pinfunction "1_1") (pintype "passive"))
      (node (ref "J4") (pin "5") (pinfunction "5_5") (pintype "passive"))
      (node (ref "J7") (pin "3") (pinfunction "3_3") (pintype "passive"))
      (node (ref "R12") (pin "1") (pinfunction "1_1") (pintype "passive"))
      (node (ref "U2") (pin "13") (pinfunction "VDDA_13") (pintype "power_in"))
    )
    (net (code "82") (name "/VIO") (class "Default")
      (node (ref "C1") (pin "2") (pinfunction "2_2") (pintype "passive"))
      (node (ref "C3") (pin "2") (pinfunction "2_2") (pintype "passive"))
      (node (ref "J4") (pin "20") (pinfunction "20_20") (pintype "passive"))
      (node (ref "R15") (pin "1") (pinfunction "1_1") (pintype "passive"))
      (node (ref "U2") (pin "32") (pinfunction "VIO_1_32") (pintype "power_in"))
      (node (ref "U2") (pin "64") (pinfunction "VIO_3_64") (pintype "power_in"))
    )
    (net (code "83") (name "3V3") (class "Default")
      (node (ref "C21") (pin "1") (pinfunction "1_1") (pintype "passive"))
      (node (ref "D2") (pin "1") (pinfunction "A_1") (pintype "passive"))
      (node (ref "D3") (pin "1") (pinfunction "A_1") (pintype "passive"))
      (node (ref "J2") (pin "7") (pinfunction "7_7") (pintype "passive"))
      (node (ref "J3") (pin "1") (pinfunction "1_1") (pintype "passive"))
      (node (ref "J3") (pin "12") (pinfunction "12_12") (pintype "passive"))
      (node (ref "J3") (pin "16") (pinfunction "16_16") (pintype "passive"))
      (node (ref "J3") (pin "2") (pinfunction "2_2") (pintype "passive"))
      (node (ref "J3") (pin "3") (pinfunction "3_3") (pintype "passive"))
      (node (ref "J3") (pin "4") (pinfunction "4_4") (pintype "passive"))
      (node (ref "J5") (pin "2") (pinfunction "2_2") (pintype "passive"))
      (node (ref "J5") (pin "4") (pinfunction "4_4") (pintype "passive"))
      (node (ref "R1") (pin "2") (pinfunction "2_2") (pintype "passive"))
      (node (ref "R14") (pin "2") (pinfunction "2_2") (pintype "passive"))
      (node (ref "R2") (pin "1") (pinfunction "1_1") (pintype "passive"))
      (node (ref "R24") (pin "2") (pinfunction "2_2") (pintype "passive"))
      (node (ref "R3") (pin "1") (pinfunction "1_1") (pintype "passive"))
      (node (ref "R7") (pin "1") (pinfunction "1_1") (pintype "passive"))
      (node (ref "S3") (pin "3") (pinfunction "3_3") (pintype "passive"))
      (node (ref "U3") (pin "14") (pinfunction "VDD33/VIO_14") (pintype "power_in"))
    )
    (net (code "84") (name "5V_in") (class "Default")
      (node (ref "F2") (pin "1") (pinfunction "1_1") (pintype "passive"))
      (node (ref "P6") (pin "A4") (pinfunction "VBUS_A4") (pintype "bidirectional"))
      (node (ref "P6") (pin "B4") (pinfunction "VBUS_B4") (pintype "bidirectional"))
      (node (ref "P7") (pin "A4") (pinfunction "VBUS_A4") (pintype "bidirectional"))
      (node (ref "P7") (pin "B4") (pinfunction "VBUS_B4") (pintype "bidirectional"))
      (node (ref "P9") (pin "A4") (pinfunction "VBUS_A4") (pintype "bidirectional"))
      (node (ref "P9") (pin "B4") (pinfunction "VBUS_B4") (pintype "bidirectional"))
    )
    (net (code "85") (name "GND") (class "Default")
      (node (ref "C1") (pin "1") (pinfunction "1_1") (pintype "passive"))
      (node (ref "C10") (pin "2") (pinfunction "2_2") (pintype "passive"))
      (node (ref "C11") (pin "1") (pinfunction "1_1") (pintype "passive"))
      (node (ref "C12") (pin "2") (pinfunction "2_2") (pintype "passive"))
      (node (ref "C13") (pin "2") (pinfunction "2_2") (pintype "passive"))
      (node (ref "C2") (pin "1") (pinfunction "1_1") (pintype "passive"))
      (node (ref "C21") (pin "2") (pinfunction "2_2") (pintype "passive"))
      (node (ref "C3") (pin "1") (pinfunction "1_1") (pintype "passive"))
      (node (ref "C31") (pin "1") (pinfunction "1_1") (pintype "passive"))
      (node (ref "C32") (pin "1") (pinfunction "1_1") (pintype "passive"))
      (node (ref "C4") (pin "1") (pinfunction "1_1") (pintype "passive"))
      (node (ref "C5") (pin "2") (pinfunction "2_2") (pintype "passive"))
      (node (ref "C6") (pin "2") (pinfunction "2_2") (pintype "passive"))
      (node (ref "C7") (pin "1") (pinfunction "1_1") (pintype "passive"))
      (node (ref "C8") (pin "1") (pinfunction "1_1") (pintype "passive"))
      (node (ref "C9") (pin "2") (pinfunction "2_2") (pintype "passive"))
      (node (ref "J2") (pin "5") (pinfunction "5_5") (pintype "passive"))
      (node (ref "J2") (pin "6") (pinfunction "6_6") (pintype "passive"))
      (node (ref "J3") (pin "19") (pinfunction "19_19") (pintype "passive"))
      (node (ref "J3") (pin "20") (pinfunction "20_20") (pintype "passive"))
      (node (ref "J3") (pin "21") (pinfunction "21_21") (pintype "passive"))
      (node (ref "J3") (pin "22") (pinfunction "22_22") (pintype "passive"))
      (node (ref "J3") (pin "7") (pinfunction "7_7") (pintype "passive"))
      (node (ref "J3") (pin "8") (pinfunction "8_8") (pintype "passive"))
      (node (ref "J4") (pin "32") (pinfunction "32_32") (pintype "passive"))
      (node (ref "J4") (pin "7") (pinfunction "7_7") (pintype "passive"))
      (node (ref "J5") (pin "6") (pinfunction "6_6") (pintype "passive"))
      (node (ref "J5") (pin "7") (pinfunction "7_7") (pintype "passive"))
      (node (ref "J7") (pin "4") (pinfunction "4_4") (pintype "passive"))
      (node (ref "P6") (pin "A1") (pinfunction "GND_A1") (pintype "bidirectional"))
      (node (ref "P6") (pin "B1") (pinfunction "GND_B1") (pintype "bidirectional"))
      (node (ref "P7") (pin "A1") (pinfunction "GND_A1") (pintype "bidirectional"))
      (node (ref "P7") (pin "B1") (pinfunction "GND_B1") (pintype "bidirectional"))
      (node (ref "P9") (pin "A1") (pinfunction "GND_A1") (pintype "bidirectional"))
      (node (ref "P9") (pin "B1") (pinfunction "GND_B1") (pintype "bidirectional"))
      (node (ref "PWR") (pin "2") (pinfunction "K_2") (pintype "passive"))
      (node (ref "R10") (pin "2") (pinfunction "2_2") (pintype "passive"))
      (node (ref "R11") (pin "2") (pinfunction "2_2") (pintype "passive"))
      (node (ref "R18") (pin "1") (pinfunction "1_1") (pintype "passive"))
      (node (ref "R21") (pin "1") (pinfunction "1_1") (pintype "passive"))
      (node (ref "R22") (pin "1") (pinfunction "1_1") (pintype "passive"))
      (node (ref "R25") (pin "1") (pinfunction "1_1") (pintype "passive"))
      (node (ref "R8") (pin "1") (pinfunction "1_1") (pintype "passive"))
      (node (ref "R9") (pin "1") (pinfunction "1_1") (pintype "passive"))
      (node (ref "S1") (pin "3") (pinfunction "B1_3") (pintype "passive"))
      (node (ref "S2") (pin "3") (pinfunction "B1_3") (pintype "passive"))
      (node (ref "S5") (pin "2") (pinfunction "2_2") (pintype "passive"))
      (node (ref "U1") (pin "1") (pinfunction "GND_1") (pintype "passive"))
      (node (ref "U2") (pin "12") (pinfunction "VSSA_12") (pintype "power_in"))
      (node (ref "U2") (pin "18") (pinfunction "VSS_4_18") (pintype "power_in"))
      (node (ref "U2") (pin "31") (pinfunction "VSS_1_31") (pintype "power_in"))
      (node (ref "U2") (pin "63") (pinfunction "VSS_3_63") (pintype "power_in"))
      (node (ref "U3") (pin "18") (pinfunction "VSS/GND_18") (pintype "power_in"))
    )
    (net (code "86") (name "Net-(D2-K)") (class "Default")
      (node (ref "D2") (pin "2") (pinfunction "K_2") (pintype "passive"))
      (node (ref "R13") (pin "2") (pinfunction "2_2") (pintype "passive"))
    )
    (net (code "87") (name "Net-(D3-K)") (class "Default")
      (node (ref "D3") (pin "2") (pinfunction "K_2") (pintype "passive"))
      (node (ref "R21") (pin "2") (pinfunction "2_2") (pintype "passive"))
    )
    (net (code "88") (name "Net-(J3-Pad6)") (class "Default")
      (node (ref "J3") (pin "6") (pinfunction "6_6") (pintype "passive"))
      (node (ref "R5") (pin "1") (pinfunction "1_1") (pintype "passive"))
    )
    (net (code "89") (name "Net-(J3-Pad10)") (class "Default")
      (node (ref "J3") (pin "10") (pinfunction "10_10") (pintype "passive"))
      (node (ref "J5") (pin "1") (pinfunction "1_1") (pintype "passive"))
    )
    (net (code "90") (name "Net-(LED1-A)") (class "Default")
      (node (ref "LED1") (pin "1") (pinfunction "A_1") (pintype "passive"))
      (node (ref "R2") (pin "2") (pinfunction "2_2") (pintype "passive"))
    )
    (net (code "91") (name "Net-(LED2-A)") (class "Default")
      (node (ref "LED2") (pin "1") (pinfunction "A_1") (pintype "passive"))
      (node (ref "R3") (pin "2") (pinfunction "2_2") (pintype "passive"))
    )
    (net (code "92") (name "Net-(P6-CC-PadA5)") (class "Default")
      (node (ref "P6") (pin "A5") (pinfunction "CC_A5") (pintype "bidirectional"))
      (node (ref "R18") (pin "2") (pinfunction "2_2") (pintype "passive"))
    )
    (net (code "93") (name "Net-(P6-CC-PadB5)") (class "Default")
      (node (ref "P6") (pin "B5") (pinfunction "CC_B5") (pintype "bidirectional"))
      (node (ref "R25") (pin "2") (pinfunction "2_2") (pintype "passive"))
    )
    (net (code "94") (name "Net-(P7-CC-PadA5)") (class "Default")
      (node (ref "P7") (pin "A5") (pinfunction "CC_A5") (pintype "bidirectional"))
      (node (ref "R8") (pin "2") (pinfunction "2_2") (pintype "passive"))
    )
    (net (code "95") (name "Net-(P7-CC-PadB5)") (class "Default")
      (node (ref "P7") (pin "B5") (pinfunction "CC_B5") (pintype "bidirectional"))
      (node (ref "R9") (pin "2") (pinfunction "2_2") (pintype "passive"))
    )
    (net (code "96") (name "Net-(P9-CC-PadA5)") (class "Default")
      (node (ref "P9") (pin "A5") (pinfunction "CC_A5") (pintype "bidirectional"))
      (node (ref "R10") (pin "1") (pinfunction "1_1") (pintype "passive"))
    )
    (net (code "97") (name "Net-(P9-CC-PadB5)") (class "Default")
      (node (ref "P9") (pin "B5") (pinfunction "CC_B5") (pintype "bidirectional"))
      (node (ref "R11") (pin "1") (pinfunction "1_1") (pintype "passive"))
    )
    (net (code "98") (name "Net-(PWR-A)") (class "Default")
      (node (ref "PWR") (pin "1") (pinfunction "A_1") (pintype "passive"))
      (node (ref "R1") (pin "1") (pinfunction "1_1") (pintype "passive"))
    )
    (net (code "99") (name "Net-(U1-VOUT)") (class "Default")
      (node (ref "C13") (pin "1") (pinfunction "1_1") (pintype "passive"))
      (node (ref "S3") (pin "1") (pinfunction "1_1") (pintype "passive"))
      (node (ref "U1") (pin "2") (pinfunction "VOUT_2") (pintype "passive"))
    )
    (net (code "100") (name "Net-(U2-VDD_2)") (class "Default")
      (node (ref "R16") (pin "2") (pinfunction "2_2") (pintype "passive"))
      (node (ref "U2") (pin "48") (pinfunction "VDD_2_48") (pintype "power_in"))
    )
    (net (code "101") (name "Net-(U2-VSS_2)") (class "Default")
      (node (ref "R22") (pin "2") (pinfunction "2_2") (pintype "passive"))
      (node (ref "U2") (pin "47") (pinfunction "VSS_2_47") (pintype "power_in"))
    )
    (net (code "102") (name "unconnected-(P6-RFU1-PadA8)") (class "Default")
      (node (ref "P6") (pin "A8") (pinfunction "RFU1_A8") (pintype "bidirectional+no_connect"))
    )
    (net (code "103") (name "unconnected-(P6-RFU1-PadB8)") (class "Default")
      (node (ref "P6") (pin "B8") (pinfunction "RFU1_B8") (pintype "bidirectional+no_connect"))
    )
    (net (code "104") (name "unconnected-(P7-RFU1-PadA8)") (class "Default")
      (node (ref "P7") (pin "A8") (pinfunction "RFU1_A8") (pintype "bidirectional+no_connect"))
    )
    (net (code "105") (name "unconnected-(P7-RFU1-PadB8)") (class "Default")
      (node (ref "P7") (pin "B8") (pinfunction "RFU1_B8") (pintype "bidirectional+no_connect"))
    )
    (net (code "106") (name "unconnected-(P9-RFU1-PadA8)") (class "Default")
      (node (ref "P9") (pin "A8") (pinfunction "RFU1_A8") (pintype "bidirectional+no_connect"))
    )
    (net (code "107") (name "unconnected-(P9-RFU1-PadB8)") (class "Default")
      (node (ref "P9") (pin "B8") (pinfunction "RFU1_B8") (pintype "bidirectional+no_connect"))
    )
    (net (code "108") (name "unconnected-(S1-A1-Pad4)") (class "Default")
      (node (ref "S1") (pin "4") (pinfunction "A1_4") (pintype "passive"))
    )
    (net (code "109") (name "unconnected-(S1-B0-Pad2)") (class "Default")
      (node (ref "S1") (pin "2") (pinfunction "B0_2") (pintype "passive"))
    )
    (net (code "110") (name "unconnected-(S2-A1-Pad4)") (class "Default")
      (node (ref "S2") (pin "4") (pinfunction "A1_4") (pintype "passive"))
    )
    (net (code "111") (name "unconnected-(S2-B0-Pad2)") (class "Default")
      (node (ref "S2") (pin "2") (pinfunction "B0_2") (pintype "passive"))
    )
    (net (code "112") (name "unconnected-(S3-Pad2)") (class "Default")
      (node (ref "S3") (pin "2") (pinfunction "2_2") (pintype "passive"))
    )
    (net (code "113") (name "unconnected-(U3-PA5{slash}UART1_CTS{slash}PA1_(no5V)-Pad2)") (class "Default")
      (node (ref "U3") (pin "2") (pinfunction "PA5/UART1_CTS/PA1_(no5V)_2") (pintype "bidirectional+no_connect"))
    )
    (net (code "114") (name "unconnected-(U3-PB12{slash}SPI2_NSS{slash}CAN2_RX-Pad5)") (class "Default")
      (node (ref "U3") (pin "5") (pinfunction "PB12/SPI2_NSS/CAN2_RX_5") (pintype "bidirectional+no_connect"))
    )
    (net (code "115") (name "unconnected-(U3-PB14{slash}SPI2_MISO{slash}UART3_RTS-Pad7)") (class "Default")
      (node (ref "U3") (pin "7") (pinfunction "PB14/SPI2_MISO/UART3_RTS_7") (pintype "bidirectional+no_connect"))
    )
    (net (code "116") (name "unconnected-(U3-PB15{slash}SPI2_MOSI{slash}UART1_TX-Pad8)") (class "Default")
      (node (ref "U3") (pin "8") (pinfunction "PB15/SPI2_MOSI/UART1_TX_8") (pintype "bidirectional+no_connect"))
    )
  )
)
